# 7-LTC2983.net
KiCad netlist of a schematic drawn in Altium Designer
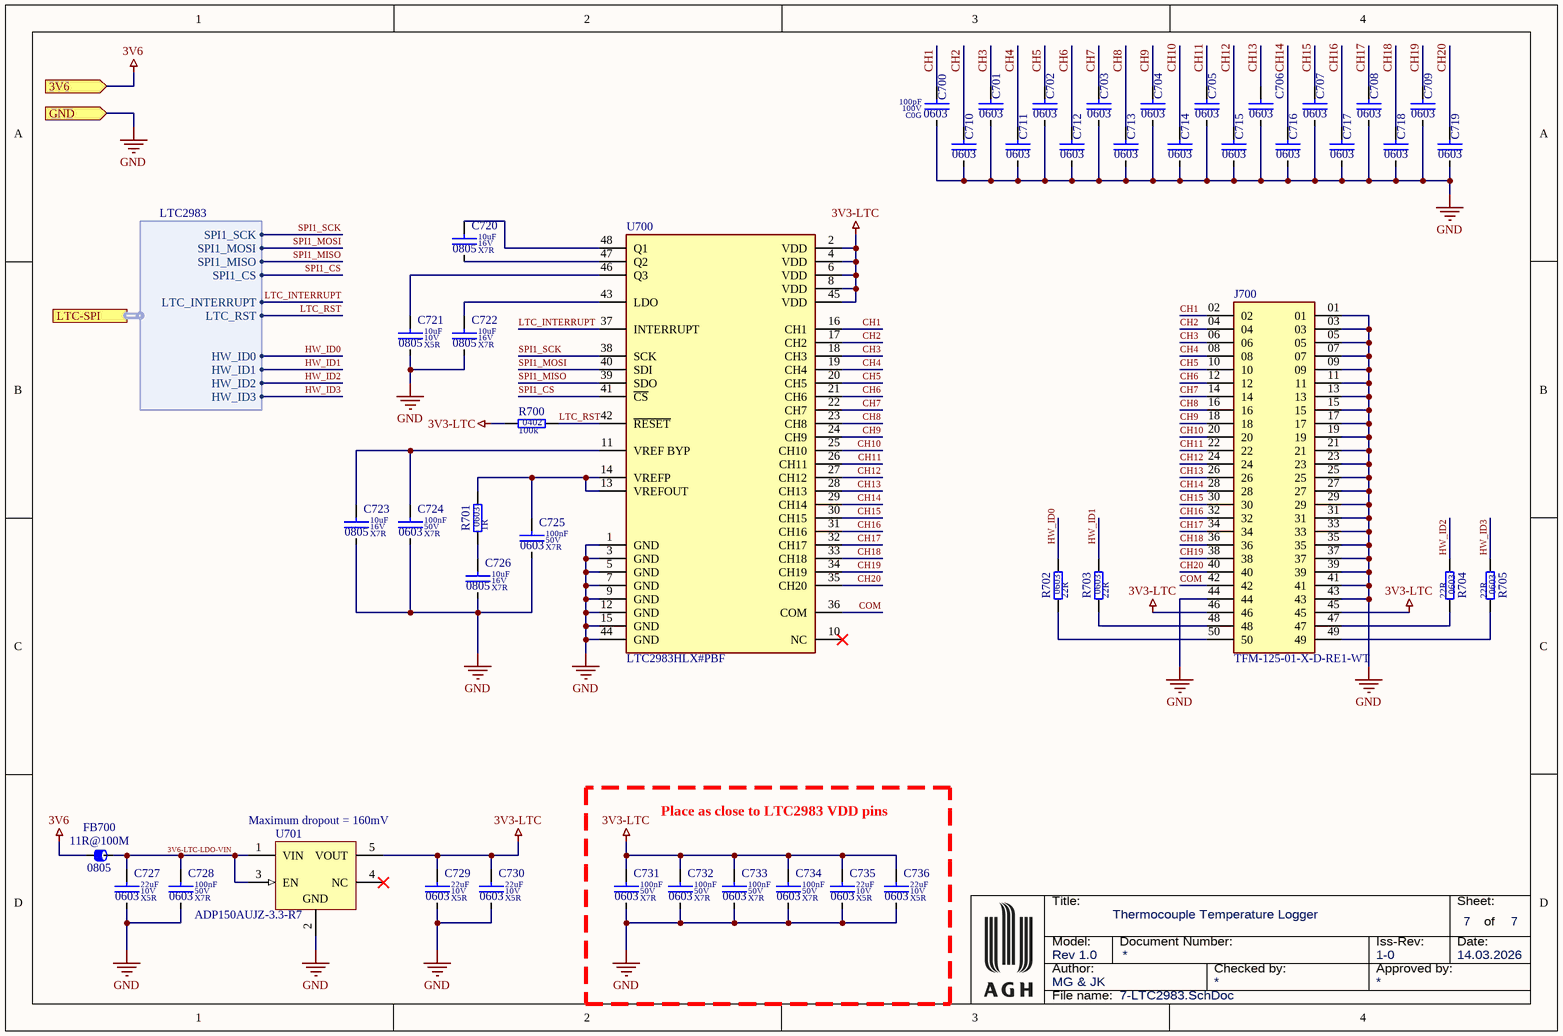
[diagram p0: 7-LTC2983.SchDoc]

(export (version "E")
  (design (tool "Eeschema 10.0.6"))
  (components
    (comp (ref "C700")
      (value "100pF")
      (footprint "C_0603_1608")
      (description "Capacitor")
      (fields
        (field (name "DIELECTRIC") "C0G")
        (field (name "VOLTAGE") "100V")
        (field (name "SCH_FOOTPRINT") "0603")
        (field (name "PART NUMBER") "C_100pF_100V_C0G_0603_5_AECQ1")
        (field (name "MANUFACTURER") "Murata")
      )
      (libsource (lib "Library") (part "C"))
    )
    (comp (ref "C701")
      (value "Ceramic C0G")
      (footprint "C_0603_1608")
      (description "Capacitor")
      (fields
        (field (name "VOLTAGE") "100V")
        (field (name "SCH_FOOTPRINT") "0603")
        (field (name "PART NUMBER") "C_100pF_100V_C0G_0603_5_AECQ1")
      )
      (libsource (lib "Library") (part "C"))
    )
    (comp (ref "C702")
      (value "Ceramic C0G")
      (footprint "C_0603_1608")
      (description "Capacitor")
      (fields
        (field (name "VOLTAGE") "100V")
        (field (name "SCH_FOOTPRINT") "0603")
        (field (name "PART NUMBER") "C_100pF_100V_C0G_0603_5_AECQ1")
      )
      (libsource (lib "Library") (part "C"))
    )
    (comp (ref "C703")
      (value "Ceramic C0G")
      (footprint "C_0603_1608")
      (description "Capacitor")
      (fields
        (field (name "VOLTAGE") "100V")
        (field (name "SCH_FOOTPRINT") "0603")
        (field (name "PART NUMBER") "C_100pF_100V_C0G_0603_5_AECQ1")
      )
      (libsource (lib "Library") (part "C"))
    )
    (comp (ref "C704")
      (value "Ceramic C0G")
      (footprint "C_0603_1608")
      (description "Capacitor")
      (fields
        (field (name "VOLTAGE") "100V")
        (field (name "SCH_FOOTPRINT") "0603")
        (field (name "PART NUMBER") "C_100pF_100V_C0G_0603_5_AECQ1")
      )
      (libsource (lib "Library") (part "C"))
    )
    (comp (ref "C705")
      (value "Ceramic C0G")
      (footprint "C_0603_1608")
      (description "Capacitor")
      (fields
        (field (name "VOLTAGE") "100V")
        (field (name "SCH_FOOTPRINT") "0603")
        (field (name "PART NUMBER") "C_100pF_100V_C0G_0603_5_AECQ1")
      )
      (libsource (lib "Library") (part "C"))
    )
    (comp (ref "C706")
      (value "Ceramic C0G")
      (footprint "C_0603_1608")
      (description "Capacitor")
      (fields
        (field (name "VOLTAGE") "100V")
        (field (name "SCH_FOOTPRINT") "0603")
        (field (name "PART NUMBER") "C_100pF_100V_C0G_0603_5_AECQ1")
      )
      (libsource (lib "Library") (part "C"))
    )
    (comp (ref "C707")
      (value "Ceramic C0G")
      (footprint "C_0603_1608")
      (description "Capacitor")
      (fields
        (field (name "VOLTAGE") "100V")
        (field (name "SCH_FOOTPRINT") "0603")
        (field (name "PART NUMBER") "C_100pF_100V_C0G_0603_5_AECQ1")
      )
      (libsource (lib "Library") (part "C"))
    )
    (comp (ref "C708")
      (value "Ceramic C0G")
      (footprint "C_0603_1608")
      (description "Capacitor")
      (fields
        (field (name "VOLTAGE") "100V")
        (field (name "SCH_FOOTPRINT") "0603")
        (field (name "PART NUMBER") "C_100pF_100V_C0G_0603_5_AECQ1")
      )
      (libsource (lib "Library") (part "C"))
    )
    (comp (ref "C709")
      (value "Ceramic C0G")
      (footprint "C_0603_1608")
      (description "Capacitor")
      (fields
        (field (name "VOLTAGE") "100V")
        (field (name "SCH_FOOTPRINT") "0603")
        (field (name "PART NUMBER") "C_100pF_100V_C0G_0603_5_AECQ1")
      )
      (libsource (lib "Library") (part "C"))
    )
    (comp (ref "C710")
      (value "Ceramic C0G")
      (footprint "C_0603_1608")
      (description "Capacitor")
      (fields
        (field (name "VOLTAGE") "100V")
        (field (name "SCH_FOOTPRINT") "0603")
        (field (name "PART NUMBER") "C_100pF_100V_C0G_0603_5_AECQ1")
      )
      (libsource (lib "Library") (part "C"))
    )
    (comp (ref "C711")
      (value "Ceramic C0G")
      (footprint "C_0603_1608")
      (description "Capacitor")
      (fields
        (field (name "VOLTAGE") "100V")
        (field (name "SCH_FOOTPRINT") "0603")
        (field (name "PART NUMBER") "C_100pF_100V_C0G_0603_5_AECQ1")
      )
      (libsource (lib "Library") (part "C"))
    )
    (comp (ref "C712")
      (value "Ceramic C0G")
      (footprint "C_0603_1608")
      (description "Capacitor")
      (fields
        (field (name "VOLTAGE") "100V")
        (field (name "SCH_FOOTPRINT") "0603")
        (field (name "PART NUMBER") "C_100pF_100V_C0G_0603_5_AECQ1")
      )
      (libsource (lib "Library") (part "C"))
    )
    (comp (ref "C713")
      (value "Ceramic C0G")
      (footprint "C_0603_1608")
      (description "Capacitor")
      (fields
        (field (name "VOLTAGE") "100V")
        (field (name "SCH_FOOTPRINT") "0603")
        (field (name "PART NUMBER") "C_100pF_100V_C0G_0603_5_AECQ1")
      )
      (libsource (lib "Library") (part "C"))
    )
    (comp (ref "C714")
      (value "Ceramic C0G")
      (footprint "C_0603_1608")
      (description "Capacitor")
      (fields
        (field (name "VOLTAGE") "100V")
        (field (name "SCH_FOOTPRINT") "0603")
        (field (name "PART NUMBER") "C_100pF_100V_C0G_0603_5_AECQ1")
      )
      (libsource (lib "Library") (part "C"))
    )
    (comp (ref "C715")
      (value "Ceramic C0G")
      (footprint "C_0603_1608")
      (description "Capacitor")
      (fields
        (field (name "VOLTAGE") "100V")
        (field (name "SCH_FOOTPRINT") "0603")
        (field (name "PART NUMBER") "C_100pF_100V_C0G_0603_5_AECQ1")
      )
      (libsource (lib "Library") (part "C"))
    )
    (comp (ref "C716")
      (value "Ceramic C0G")
      (footprint "C_0603_1608")
      (description "Capacitor")
      (fields
        (field (name "VOLTAGE") "100V")
        (field (name "SCH_FOOTPRINT") "0603")
        (field (name "PART NUMBER") "C_100pF_100V_C0G_0603_5_AECQ1")
      )
      (libsource (lib "Library") (part "C"))
    )
    (comp (ref "C717")
      (value "Ceramic C0G")
      (footprint "C_0603_1608")
      (description "Capacitor")
      (fields
        (field (name "VOLTAGE") "100V")
        (field (name "SCH_FOOTPRINT") "0603")
        (field (name "PART NUMBER") "C_100pF_100V_C0G_0603_5_AECQ1")
      )
      (libsource (lib "Library") (part "C"))
    )
    (comp (ref "C718")
      (value "Ceramic C0G")
      (footprint "C_0603_1608")
      (description "Capacitor")
      (fields
        (field (name "VOLTAGE") "100V")
        (field (name "SCH_FOOTPRINT") "0603")
        (field (name "PART NUMBER") "C_100pF_100V_C0G_0603_5_AECQ1")
      )
      (libsource (lib "Library") (part "C"))
    )
    (comp (ref "C719")
      (value "Ceramic C0G")
      (footprint "C_0603_1608")
      (description "Capacitor")
      (fields
        (field (name "VOLTAGE") "100V")
        (field (name "SCH_FOOTPRINT") "0603")
        (field (name "PART NUMBER") "C_100pF_100V_C0G_0603_5_AECQ1")
      )
      (libsource (lib "Library") (part "C"))
    )
    (comp (ref "C720")
      (value "10uF")
      (footprint "C_0805_2012")
      (description "Capacitor")
      (fields
        (field (name "DIELECTRIC") "X7R")
        (field (name "VOLTAGE") "16V")
        (field (name "SCH_FOOTPRINT") "0805")
        (field (name "PART NUMBER") "C_10uF_16V_X7R_0805_10")
        (field (name "MANUFACTURER") "Taiyo Yuden")
      )
      (libsource (lib "Library") (part "C"))
    )
    (comp (ref "C721")
      (value "10uF")
      (footprint "C_0805_2012")
      (description "Capacitor")
      (fields
        (field (name "DIELECTRIC") "X5R")
        (field (name "VOLTAGE") "10V")
        (field (name "SCH_FOOTPRINT") "0805")
        (field (name "PART NUMBER") "C_10uF_10V_X5R_0805_10")
        (field (name "MANUFACTURER") "Kemet")
      )
      (libsource (lib "Library") (part "C"))
    )
    (comp (ref "C722")
      (value "10uF")
      (footprint "C_0805_2012")
      (description "Capacitor")
      (fields
        (field (name "DIELECTRIC") "X7R")
        (field (name "VOLTAGE") "16V")
        (field (name "SCH_FOOTPRINT") "0805")
        (field (name "PART NUMBER") "C_10uF_16V_X7R_0805_10")
        (field (name "MANUFACTURER") "Taiyo Yuden")
      )
      (libsource (lib "Library") (part "C"))
    )
    (comp (ref "C723")
      (value "10uF")
      (footprint "C_0805_2012")
      (description "Capacitor")
      (fields
        (field (name "DIELECTRIC") "X7R")
        (field (name "VOLTAGE") "16V")
        (field (name "SCH_FOOTPRINT") "0805")
        (field (name "PART NUMBER") "C_10uF_16V_X7R_0805_10")
        (field (name "MANUFACTURER") "Taiyo Yuden")
      )
      (libsource (lib "Library") (part "C"))
    )
    (comp (ref "C724")
      (value "100nF")
      (footprint "C_0603_1608")
      (description "Capacitor")
      (fields
        (field (name "DIELECTRIC") "X7R")
        (field (name "VOLTAGE") "50V")
        (field (name "SCH_FOOTPRINT") "0603")
        (field (name "PART NUMBER") "C_100nF_50V_X7R_0603_10_AECQ1")
        (field (name "MANUFACTURER") "Murata")
      )
      (libsource (lib "Library") (part "C"))
    )
    (comp (ref "C725")
      (value "100nF")
      (footprint "C_0603_1608")
      (description "Capacitor")
      (fields
        (field (name "DIELECTRIC") "X7R")
        (field (name "VOLTAGE") "50V")
        (field (name "SCH_FOOTPRINT") "0603")
        (field (name "PART NUMBER") "C_100nF_50V_X7R_0603_10_AECQ1")
        (field (name "MANUFACTURER") "Murata")
      )
      (libsource (lib "Library") (part "C"))
    )
    (comp (ref "C726")
      (value "10uF")
      (footprint "C_0805_2012")
      (description "Capacitor")
      (fields
        (field (name "DIELECTRIC") "X7R")
        (field (name "VOLTAGE") "16V")
        (field (name "SCH_FOOTPRINT") "0805")
        (field (name "PART NUMBER") "C_10uF_16V_X7R_0805_10")
        (field (name "MANUFACTURER") "Taiyo Yuden")
      )
      (libsource (lib "Library") (part "C"))
    )
    (comp (ref "C727")
      (value "22uF")
      (footprint "C_0603_1608")
      (description "Capacitor")
      (fields
        (field (name "DIELECTRIC") "X5R")
        (field (name "VOLTAGE") "10V")
        (field (name "SCH_FOOTPRINT") "0603")
        (field (name "PART NUMBER") "C_22uF_10V_X5R_0603_20")
        (field (name "MANUFACTURER") "Murata")
      )
      (libsource (lib "Library") (part "C"))
    )
    (comp (ref "C728")
      (value "100nF")
      (footprint "C_0603_1608")
      (description "Capacitor")
      (fields
        (field (name "DIELECTRIC") "X7R")
        (field (name "VOLTAGE") "50V")
        (field (name "SCH_FOOTPRINT") "0603")
        (field (name "PART NUMBER") "C_100nF_50V_X7R_0603_10_AECQ1")
        (field (name "MANUFACTURER") "Murata")
      )
      (libsource (lib "Library") (part "C"))
    )
    (comp (ref "C729")
      (value "22uF")
      (footprint "C_0603_1608")
      (description "Capacitor")
      (fields
        (field (name "DIELECTRIC") "X5R")
        (field (name "VOLTAGE") "10V")
        (field (name "SCH_FOOTPRINT") "0603")
        (field (name "PART NUMBER") "C_22uF_10V_X5R_0603_20")
        (field (name "MANUFACTURER") "Murata")
      )
      (libsource (lib "Library") (part "C"))
    )
    (comp (ref "C730")
      (value "22uF")
      (footprint "C_0603_1608")
      (description "Capacitor")
      (fields
        (field (name "DIELECTRIC") "X5R")
        (field (name "VOLTAGE") "10V")
        (field (name "SCH_FOOTPRINT") "0603")
        (field (name "PART NUMBER") "C_22uF_10V_X5R_0603_20")
        (field (name "MANUFACTURER") "Murata")
      )
      (libsource (lib "Library") (part "C"))
    )
    (comp (ref "C731")
      (value "100nF")
      (footprint "C_0603_1608")
      (description "Capacitor")
      (fields
        (field (name "DIELECTRIC") "X7R")
        (field (name "VOLTAGE") "50V")
        (field (name "SCH_FOOTPRINT") "0603")
        (field (name "PART NUMBER") "C_100nF_50V_X7R_0603_10_AECQ1")
        (field (name "MANUFACTURER") "Murata")
      )
      (libsource (lib "Library") (part "C"))
    )
    (comp (ref "C732")
      (value "100nF")
      (footprint "C_0603_1608")
      (description "Capacitor")
      (fields
        (field (name "DIELECTRIC") "X7R")
        (field (name "VOLTAGE") "50V")
        (field (name "SCH_FOOTPRINT") "0603")
        (field (name "PART NUMBER") "C_100nF_50V_X7R_0603_10_AECQ1")
        (field (name "MANUFACTURER") "Murata")
      )
      (libsource (lib "Library") (part "C"))
    )
    (comp (ref "C733")
      (value "100nF")
      (footprint "C_0603_1608")
      (description "Capacitor")
      (fields
        (field (name "DIELECTRIC") "X7R")
        (field (name "VOLTAGE") "50V")
        (field (name "SCH_FOOTPRINT") "0603")
        (field (name "PART NUMBER") "C_100nF_50V_X7R_0603_10_AECQ1")
        (field (name "MANUFACTURER") "Murata")
      )
      (libsource (lib "Library") (part "C"))
    )
    (comp (ref "C734")
      (value "100nF")
      (footprint "C_0603_1608")
      (description "Capacitor")
      (fields
        (field (name "DIELECTRIC") "X7R")
        (field (name "VOLTAGE") "50V")
        (field (name "SCH_FOOTPRINT") "0603")
        (field (name "PART NUMBER") "C_100nF_50V_X7R_0603_10_AECQ1")
        (field (name "MANUFACTURER") "Murata")
      )
      (libsource (lib "Library") (part "C"))
    )
    (comp (ref "C735")
      (value "22uF")
      (footprint "C_0603_1608")
      (description "Capacitor")
      (fields
        (field (name "DIELECTRIC") "X5R")
        (field (name "VOLTAGE") "10V")
        (field (name "SCH_FOOTPRINT") "0603")
        (field (name "PART NUMBER") "C_22uF_10V_X5R_0603_20")
        (field (name "MANUFACTURER") "Murata")
      )
      (libsource (lib "Library") (part "C"))
    )
    (comp (ref "C736")
      (value "22uF")
      (footprint "C_0603_1608")
      (description "Capacitor")
      (fields
        (field (name "DIELECTRIC") "X5R")
        (field (name "VOLTAGE") "10V")
        (field (name "SCH_FOOTPRINT") "0603")
        (field (name "PART NUMBER") "C_22uF_10V_X5R_0603_20")
        (field (name "MANUFACTURER") "Murata")
      )
      (libsource (lib "Library") (part "C"))
    )
    (comp (ref "FB700")
      (value "11R@100M")
      (footprint "FB_0805_2012")
      (description "Ferrite Bead")
      (fields
        (field (name "SCH_FOOTPRINT") "0805")
        (field (name "PART NUMBER") "FB_2508051107Y0")
        (field (name "MANUFACTURER") "Fair-Rite")
      )
      (libsource (lib "Library") (part "FB"))
    )
    (comp (ref "J700")
      (value "TFM-125-01-X-D-RE1-WT")
      (footprint "SAMTEC_TFM-125-01-X-D-RE1-WT")
      (fields (field (name "MF") "Samtec"))
      (libsource (lib "TFM-125-01-X-D-RE1-WT") (part "TFM-125-01-X-D-RE1-WT"))
    )
    (comp (ref "R700")
      (value "100k")
      (footprint "R_0402_1005")
      (fields
        (field (name "SCH_FOOTPRINT") "0402")
        (field (name "PART NUMBER") "R_100k_0402_1")
        (field (name "VOLTAGE") "50V")
        (field (name "POWER") "63mW")
      )
      (libsource (lib "Library") (part "R"))
    )
    (comp (ref "R701")
      (value "1R")
      (footprint "R_0603_1608")
      (fields
        (field (name "SCH_FOOTPRINT") "0603")
        (field (name "PART NUMBER") "R_1R_0603_1")
        (field (name "VOLTAGE") "50V")
        (field (name "POWER") "100mW")
      )
      (libsource (lib "Library") (part "R"))
    )
    (comp (ref "R702")
      (value "22R")
      (footprint "R_0603_1608")
      (fields
        (field (name "SCH_FOOTPRINT") "0603")
        (field (name "PART NUMBER") "R_22R_0603_5")
        (field (name "VOLTAGE") "50V")
        (field (name "POWER") "125mW")
      )
      (libsource (lib "Library") (part "R"))
    )
    (comp (ref "R703")
      (value "22R")
      (footprint "R_0603_1608")
      (fields
        (field (name "SCH_FOOTPRINT") "0603")
        (field (name "PART NUMBER") "R_22R_0603_5")
        (field (name "VOLTAGE") "50V")
        (field (name "POWER") "125mW")
      )
      (libsource (lib "Library") (part "R"))
    )
    (comp (ref "R704")
      (value "22R")
      (footprint "R_0603_1608")
      (fields
        (field (name "SCH_FOOTPRINT") "0603")
        (field (name "PART NUMBER") "R_22R_0603_5")
        (field (name "VOLTAGE") "50V")
        (field (name "POWER") "125mW")
      )
      (libsource (lib "Library") (part "R"))
    )
    (comp (ref "R705")
      (value "22R")
      (footprint "R_0603_1608")
      (fields
        (field (name "SCH_FOOTPRINT") "0603")
        (field (name "PART NUMBER") "R_22R_0603_5")
        (field (name "VOLTAGE") "50V")
        (field (name "POWER") "125mW")
      )
      (libsource (lib "Library") (part "R"))
    )
    (comp (ref "U700")
      (value "LTC2983HLX#PBF")
      (footprint "FP-LX-48-05-08-1760-MFG")
      (description "MULTI SENSOR HIGH ACCURACY DIGIT")
      (libsource (lib "Altium Content Vault") (part "619e390301cc7b64d01bc91c6dc15a9"))
    )
    (comp (ref "U701")
      (value "ADP150AUJZ-3.3-R7")
      (footprint "ADI-UJ-5_M")
      (fields (field (name "MANUFACTURER") "Analog Devices"))
      (libsource (lib "Altium Content Vault") (part "ADI-ADP1XX-UJ-5"))
    )
  )
  (nets
    (net (code "2") (name "/3V6-LTC-LDO-VIN") (class "Default")
      (node (ref "C727") (pin "1") (pinfunction "1_1") (pintype "passive"))
      (node (ref "C728") (pin "1") (pinfunction "1_1") (pintype "passive"))
      (node (ref "FB700") (pin "2") (pintype "passive"))
      (node (ref "U701") (pin "1") (pinfunction "VIN_1") (pintype "power_in"))
      (node (ref "U701") (pin "3") (pinfunction "EN_3") (pintype "input"))
    )
    (net (code "3") (name "/CH1") (class "Default")
      (node (ref "C700") (pin "1") (pinfunction "1_1") (pintype "passive"))
      (node (ref "J700") (pin "02") (pinfunction "02_02") (pintype "passive"))
      (node (ref "U700") (pin "16") (pinfunction "CH1_16") (pintype "passive"))
    )
    (net (code "4") (name "/CH2") (class "Default")
      (node (ref "C710") (pin "1") (pinfunction "1_1") (pintype "passive"))
      (node (ref "J700") (pin "04") (pinfunction "04_04") (pintype "passive"))
      (node (ref "U700") (pin "17") (pinfunction "CH2_17") (pintype "passive"))
    )
    (net (code "5") (name "/CH3") (class "Default")
      (node (ref "C701") (pin "1") (pinfunction "1_1") (pintype "passive"))
      (node (ref "J700") (pin "06") (pinfunction "06_06") (pintype "passive"))
      (node (ref "U700") (pin "18") (pinfunction "CH3_18") (pintype "passive"))
    )
    (net (code "6") (name "/CH4") (class "Default")
      (node (ref "C711") (pin "1") (pinfunction "1_1") (pintype "passive"))
      (node (ref "J700") (pin "08") (pinfunction "08_08") (pintype "passive"))
      (node (ref "U700") (pin "19") (pinfunction "CH4_19") (pintype "passive"))
    )
    (net (code "7") (name "/CH5") (class "Default")
      (node (ref "C702") (pin "1") (pinfunction "1_1") (pintype "passive"))
      (node (ref "J700") (pin "10") (pinfunction "10_10") (pintype "passive"))
      (node (ref "U700") (pin "20") (pinfunction "CH5_20") (pintype "passive"))
    )
    (net (code "8") (name "/CH6") (class "Default")
      (node (ref "C712") (pin "1") (pinfunction "1_1") (pintype "passive"))
      (node (ref "J700") (pin "12") (pinfunction "12_12") (pintype "passive"))
      (node (ref "U700") (pin "21") (pinfunction "CH6_21") (pintype "passive"))
    )
    (net (code "9") (name "/CH7") (class "Default")
      (node (ref "C703") (pin "1") (pinfunction "1_1") (pintype "passive"))
      (node (ref "J700") (pin "14") (pinfunction "14_14") (pintype "passive"))
      (node (ref "U700") (pin "22") (pinfunction "CH7_22") (pintype "passive"))
    )
    (net (code "10") (name "/CH8") (class "Default")
      (node (ref "C713") (pin "1") (pinfunction "1_1") (pintype "passive"))
      (node (ref "J700") (pin "16") (pinfunction "16_16") (pintype "passive"))
      (node (ref "U700") (pin "23") (pinfunction "CH8_23") (pintype "passive"))
    )
    (net (code "11") (name "/CH9") (class "Default")
      (node (ref "C704") (pin "1") (pinfunction "1_1") (pintype "passive"))
      (node (ref "J700") (pin "18") (pinfunction "18_18") (pintype "passive"))
      (node (ref "U700") (pin "24") (pinfunction "CH9_24") (pintype "passive"))
    )
    (net (code "12") (name "/CH10") (class "Default")
      (node (ref "C714") (pin "1") (pinfunction "1_1") (pintype "passive"))
      (node (ref "J700") (pin "20") (pinfunction "20_20") (pintype "passive"))
      (node (ref "U700") (pin "25") (pinfunction "CH10_25") (pintype "passive"))
    )
    (net (code "13") (name "/CH11") (class "Default")
      (node (ref "C705") (pin "1") (pinfunction "1_1") (pintype "passive"))
      (node (ref "J700") (pin "22") (pinfunction "22_22") (pintype "passive"))
      (node (ref "U700") (pin "26") (pinfunction "CH11_26") (pintype "passive"))
    )
    (net (code "14") (name "/CH12") (class "Default")
      (node (ref "C715") (pin "1") (pinfunction "1_1") (pintype "passive"))
      (node (ref "J700") (pin "24") (pinfunction "24_24") (pintype "passive"))
      (node (ref "U700") (pin "27") (pinfunction "CH12_27") (pintype "passive"))
    )
    (net (code "15") (name "/CH13") (class "Default")
      (node (ref "C706") (pin "1") (pinfunction "1_1") (pintype "passive"))
      (node (ref "J700") (pin "26") (pinfunction "26_26") (pintype "passive"))
      (node (ref "U700") (pin "28") (pinfunction "CH13_28") (pintype "passive"))
    )
    (net (code "16") (name "/CH14") (class "Default")
      (node (ref "C716") (pin "1") (pinfunction "1_1") (pintype "passive"))
      (node (ref "J700") (pin "28") (pinfunction "28_28") (pintype "passive"))
      (node (ref "U700") (pin "29") (pinfunction "CH14_29") (pintype "passive"))
    )
    (net (code "17") (name "/CH15") (class "Default")
      (node (ref "C707") (pin "1") (pinfunction "1_1") (pintype "passive"))
      (node (ref "J700") (pin "30") (pinfunction "30_30") (pintype "passive"))
      (node (ref "U700") (pin "30") (pinfunction "CH15_30") (pintype "passive"))
    )
    (net (code "18") (name "/CH16") (class "Default")
      (node (ref "C717") (pin "1") (pinfunction "1_1") (pintype "passive"))
      (node (ref "J700") (pin "32") (pinfunction "32_32") (pintype "passive"))
      (node (ref "U700") (pin "31") (pinfunction "CH16_31") (pintype "passive"))
    )
    (net (code "19") (name "/CH17") (class "Default")
      (node (ref "C708") (pin "1") (pinfunction "1_1") (pintype "passive"))
      (node (ref "J700") (pin "34") (pinfunction "34_34") (pintype "passive"))
      (node (ref "U700") (pin "32") (pinfunction "CH17_32") (pintype "passive"))
    )
    (net (code "20") (name "/CH18") (class "Default")
      (node (ref "C718") (pin "1") (pinfunction "1_1") (pintype "passive"))
      (node (ref "J700") (pin "36") (pinfunction "36_36") (pintype "passive"))
      (node (ref "U700") (pin "33") (pinfunction "CH18_33") (pintype "passive"))
    )
    (net (code "21") (name "/CH19") (class "Default")
      (node (ref "C709") (pin "1") (pinfunction "1_1") (pintype "passive"))
      (node (ref "J700") (pin "38") (pinfunction "38_38") (pintype "passive"))
      (node (ref "U700") (pin "34") (pinfunction "CH19_34") (pintype "passive"))
    )
    (net (code "22") (name "/CH20") (class "Default")
      (node (ref "C719") (pin "1") (pinfunction "1_1") (pintype "passive"))
      (node (ref "J700") (pin "40") (pinfunction "40_40") (pintype "passive"))
      (node (ref "U700") (pin "35") (pinfunction "CH20_35") (pintype "passive"))
    )
    (net (code "23") (name "/COM") (class "Default")
      (node (ref "J700") (pin "42") (pinfunction "42_42") (pintype "passive"))
      (node (ref "U700") (pin "36") (pinfunction "COM_36") (pintype "passive"))
    )
    (net (code "24") (name "/HW_ID0") (class "Default")
      (node (ref "R702") (pin "2") (pinfunction "2_2") (pintype "passive"))
    )
    (net (code "25") (name "/HW_ID1") (class "Default")
      (node (ref "R703") (pin "2") (pinfunction "2_2") (pintype "passive"))
    )
    (net (code "26") (name "/HW_ID2") (class "Default")
      (node (ref "R704") (pin "2") (pinfunction "2_2") (pintype "passive"))
    )
    (net (code "27") (name "/HW_ID3") (class "Default")
      (node (ref "R705") (pin "2") (pinfunction "2_2") (pintype "passive"))
    )
    (net (code "28") (name "/LTC_INTERRUPT") (class "Default")
      (node (ref "U700") (pin "37") (pinfunction "INTERRUPT_37") (pintype "passive"))
    )
    (net (code "29") (name "/LTC_RST") (class "Default")
      (node (ref "R700") (pin "2") (pinfunction "2_2") (pintype "passive"))
      (node (ref "U700") (pin "42") (pinfunction "~{RESET}_42") (pintype "passive"))
    )
    (net (code "30") (name "/SPI1_CS") (class "Default")
      (node (ref "U700") (pin "41") (pinfunction "~{CS}_41") (pintype "passive"))
    )
    (net (code "31") (name "/SPI1_MISO") (class "Default")
      (node (ref "U700") (pin "39") (pinfunction "SDO_39") (pintype "passive"))
    )
    (net (code "32") (name "/SPI1_MOSI") (class "Default")
      (node (ref "U700") (pin "40") (pinfunction "SDI_40") (pintype "passive"))
    )
    (net (code "33") (name "/SPI1_SCK") (class "Default")
      (node (ref "U700") (pin "38") (pinfunction "SCK_38") (pintype "passive"))
    )
    (net (code "35") (name "3V3-LTC") (class "Default")
      (node (ref "C729") (pin "1") (pinfunction "1_1") (pintype "passive"))
      (node (ref "C730") (pin "1") (pinfunction "1_1") (pintype "passive"))
      (node (ref "C731") (pin "1") (pinfunction "1_1") (pintype "passive"))
      (node (ref "C732") (pin "1") (pinfunction "1_1") (pintype "passive"))
      (node (ref "C733") (pin "1") (pinfunction "1_1") (pintype "passive"))
      (node (ref "C734") (pin "1") (pinfunction "1_1") (pintype "passive"))
      (node (ref "C735") (pin "1") (pinfunction "1_1") (pintype "passive"))
      (node (ref "C736") (pin "1") (pinfunction "1_1") (pintype "passive"))
      (node (ref "J700") (pin "45") (pinfunction "45_45") (pintype "passive"))
      (node (ref "J700") (pin "46") (pinfunction "46_46") (pintype "passive"))
      (node (ref "R700") (pin "1") (pinfunction "1_1") (pintype "passive"))
      (node (ref "U700") (pin "2") (pinfunction "VDD_2") (pintype "passive"))
      (node (ref "U700") (pin "4") (pinfunction "VDD_4") (pintype "passive"))
      (node (ref "U700") (pin "45") (pinfunction "VDD_45") (pintype "passive"))
      (node (ref "U700") (pin "6") (pinfunction "VDD_6") (pintype "passive"))
      (node (ref "U700") (pin "8") (pinfunction "VDD_8") (pintype "passive"))
      (node (ref "U701") (pin "5") (pinfunction "VOUT_5") (pintype "power_in"))
    )
    (net (code "36") (name "3V6") (class "Default") (node (ref "FB700") (pin "1") (pintype "passive")))
    (net (code "37") (name "GND") (class "Default")
      (node (ref "C700") (pin "2") (pinfunction "2_2") (pintype "passive"))
      (node (ref "C701") (pin "2") (pinfunction "2_2") (pintype "passive"))
      (node (ref "C702") (pin "2") (pinfunction "2_2") (pintype "passive"))
      (node (ref "C703") (pin "2") (pinfunction "2_2") (pintype "passive"))
      (node (ref "C704") (pin "2") (pinfunction "2_2") (pintype "passive"))
      (node (ref "C705") (pin "2") (pinfunction "2_2") (pintype "passive"))
      (node (ref "C706") (pin "2") (pinfunction "2_2") (pintype "passive"))
      (node (ref "C707") (pin "2") (pinfunction "2_2") (pintype "passive"))
      (node (ref "C708") (pin "2") (pinfunction "2_2") (pintype "passive"))
      (node (ref "C709") (pin "2") (pinfunction "2_2") (pintype "passive"))
      (node (ref "C710") (pin "2") (pinfunction "2_2") (pintype "passive"))
      (node (ref "C711") (pin "2") (pinfunction "2_2") (pintype "passive"))
      (node (ref "C712") (pin "2") (pinfunction "2_2") (pintype "passive"))
      (node (ref "C713") (pin "2") (pinfunction "2_2") (pintype "passive"))
      (node (ref "C714") (pin "2") (pinfunction "2_2") (pintype "passive"))
      (node (ref "C715") (pin "2") (pinfunction "2_2") (pintype "passive"))
      (node (ref "C716") (pin "2") (pinfunction "2_2") (pintype "passive"))
      (node (ref "C717") (pin "2") (pinfunction "2_2") (pintype "passive"))
      (node (ref "C718") (pin "2") (pinfunction "2_2") (pintype "passive"))
      (node (ref "C719") (pin "2") (pinfunction "2_2") (pintype "passive"))
      (node (ref "C721") (pin "2") (pinfunction "2_2") (pintype "passive"))
      (node (ref "C722") (pin "2") (pinfunction "2_2") (pintype "passive"))
      (node (ref "C723") (pin "2") (pinfunction "2_2") (pintype "passive"))
      (node (ref "C724") (pin "2") (pinfunction "2_2") (pintype "passive"))
      (node (ref "C725") (pin "2") (pinfunction "2_2") (pintype "passive"))
      (node (ref "C726") (pin "2") (pinfunction "2_2") (pintype "passive"))
      (node (ref "C727") (pin "2") (pinfunction "2_2") (pintype "passive"))
      (node (ref "C728") (pin "2") (pinfunction "2_2") (pintype "passive"))
      (node (ref "C729") (pin "2") (pinfunction "2_2") (pintype "passive"))
      (node (ref "C730") (pin "2") (pinfunction "2_2") (pintype "passive"))
      (node (ref "C731") (pin "2") (pinfunction "2_2") (pintype "passive"))
      (node (ref "C732") (pin "2") (pinfunction "2_2") (pintype "passive"))
      (node (ref "C733") (pin "2") (pinfunction "2_2") (pintype "passive"))
      (node (ref "C734") (pin "2") (pinfunction "2_2") (pintype "passive"))
      (node (ref "C735") (pin "2") (pinfunction "2_2") (pintype "passive"))
      (node (ref "C736") (pin "2") (pinfunction "2_2") (pintype "passive"))
      (node (ref "J700") (pin "01") (pinfunction "01_01") (pintype "passive"))
      (node (ref "J700") (pin "03") (pinfunction "03_03") (pintype "passive"))
      (node (ref "J700") (pin "05") (pinfunction "05_05") (pintype "passive"))
      (node (ref "J700") (pin "07") (pinfunction "07_07") (pintype "passive"))
      (node (ref "J700") (pin "09") (pinfunction "09_09") (pintype "passive"))
      (node (ref "J700") (pin "11") (pinfunction "11_11") (pintype "passive"))
      (node (ref "J700") (pin "13") (pinfunction "13_13") (pintype "passive"))
      (node (ref "J700") (pin "15") (pinfunction "15_15") (pintype "passive"))
      (node (ref "J700") (pin "17") (pinfunction "17_17") (pintype "passive"))
      (node (ref "J700") (pin "19") (pinfunction "19_19") (pintype "passive"))
      (node (ref "J700") (pin "21") (pinfunction "21_21") (pintype "passive"))
      (node (ref "J700") (pin "23") (pinfunction "23_23") (pintype "passive"))
      (node (ref "J700") (pin "25") (pinfunction "25_25") (pintype "passive"))
      (node (ref "J700") (pin "27") (pinfunction "27_27") (pintype "passive"))
      (node (ref "J700") (pin "29") (pinfunction "29_29") (pintype "passive"))
      (node (ref "J700") (pin "31") (pinfunction "31_31") (pintype "passive"))
      (node (ref "J700") (pin "33") (pinfunction "33_33") (pintype "passive"))
      (node (ref "J700") (pin "35") (pinfunction "35_35") (pintype "passive"))
      (node (ref "J700") (pin "37") (pinfunction "37_37") (pintype "passive"))
      (node (ref "J700") (pin "39") (pinfunction "39_39") (pintype "passive"))
      (node (ref "J700") (pin "41") (pinfunction "41_41") (pintype "passive"))
      (node (ref "J700") (pin "43") (pinfunction "43_43") (pintype "passive"))
      (node (ref "J700") (pin "44") (pinfunction "44_44") (pintype "passive"))
      (node (ref "U700") (pin "1") (pinfunction "GND_1") (pintype "passive"))
      (node (ref "U700") (pin "12") (pinfunction "GND_12") (pintype "passive"))
      (node (ref "U700") (pin "15") (pinfunction "GND_15") (pintype "passive"))
      (node (ref "U700") (pin "3") (pinfunction "GND_3") (pintype "passive"))
      (node (ref "U700") (pin "44") (pinfunction "GND_44") (pintype "passive"))
      (node (ref "U700") (pin "5") (pinfunction "GND_5") (pintype "passive"))
      (node (ref "U700") (pin "7") (pinfunction "GND_7") (pintype "passive"))
      (node (ref "U700") (pin "9") (pinfunction "GND_9") (pintype "passive"))
      (node (ref "U701") (pin "2") (pinfunction "GND_2") (pintype "passive"))
    )
    (net (code "38") (name "Net-(C726-Pad1)") (class "Default")
      (node (ref "C726") (pin "1") (pinfunction "1_1") (pintype "passive"))
      (node (ref "R701") (pin "1") (pinfunction "1_1") (pintype "passive"))
    )
    (net (code "39") (name "Net-(J700-Pad47)") (class "Default")
      (node (ref "J700") (pin "47") (pinfunction "47_47") (pintype "passive"))
      (node (ref "R704") (pin "1") (pinfunction "1_1") (pintype "passive"))
    )
    (net (code "40") (name "Net-(J700-Pad48)") (class "Default")
      (node (ref "J700") (pin "48") (pinfunction "48_48") (pintype "passive"))
      (node (ref "R703") (pin "1") (pinfunction "1_1") (pintype "passive"))
    )
    (net (code "41") (name "Net-(J700-Pad49)") (class "Default")
      (node (ref "J700") (pin "49") (pinfunction "49_49") (pintype "passive"))
      (node (ref "R705") (pin "1") (pinfunction "1_1") (pintype "passive"))
    )
    (net (code "42") (name "Net-(J700-Pad50)") (class "Default")
      (node (ref "J700") (pin "50") (pinfunction "50_50") (pintype "passive"))
      (node (ref "R702") (pin "1") (pinfunction "1_1") (pintype "passive"))
    )
    (net (code "43") (name "Net-(U700-LDO)") (class "Default")
      (node (ref "C722") (pin "1") (pinfunction "1_1") (pintype "passive"))
      (node (ref "U700") (pin "43") (pinfunction "LDO_43") (pintype "passive"))
    )
    (net (code "44") (name "Net-(U700-Q1)") (class "Default")
      (node (ref "C720") (pin "1") (pinfunction "1_1") (pintype "passive"))
      (node (ref "U700") (pin "48") (pinfunction "Q1_48") (pintype "passive"))
    )
    (net (code "45") (name "Net-(U700-Q2)") (class "Default")
      (node (ref "C720") (pin "2") (pinfunction "2_2") (pintype "passive"))
      (node (ref "U700") (pin "47") (pinfunction "Q2_47") (pintype "passive"))
    )
    (net (code "46") (name "Net-(U700-Q3)") (class "Default")
      (node (ref "C721") (pin "1") (pinfunction "1_1") (pintype "passive"))
      (node (ref "U700") (pin "46") (pinfunction "Q3_46") (pintype "passive"))
    )
    (net (code "47") (name "Net-(U700-VREFOUT)") (class "Default")
      (node (ref "C725") (pin "1") (pinfunction "1_1") (pintype "passive"))
      (node (ref "R701") (pin "2") (pinfunction "2_2") (pintype "passive"))
      (node (ref "U700") (pin "13") (pinfunction "VREFOUT_13") (pintype "passive"))
      (node (ref "U700") (pin "14") (pinfunction "VREFP_14") (pintype "passive"))
    )
    (net (code "48") (name "Net-(U700-VREF_BYP)") (class "Default")
      (node (ref "C723") (pin "1") (pinfunction "1_1") (pintype "passive"))
      (node (ref "C724") (pin "1") (pinfunction "1_1") (pintype "passive"))
      (node (ref "U700") (pin "11") (pinfunction "VREF_BYP_11") (pintype "passive"))
    )
    (net (code "49") (name "unconnected-(U700-NC-Pad10)") (class "Default")
      (node (ref "U700") (pin "10") (pinfunction "NC_10") (pintype "passive+no_connect"))
    )
    (net (code "50") (name "unconnected-(U701-NC-Pad4)") (class "Default")
      (node (ref "U701") (pin "4") (pinfunction "NC_4") (pintype "passive+no_connect"))
    )
  )
)
